# discretefpga.net
KiCad netlist of a schematic drawn in EAGLE
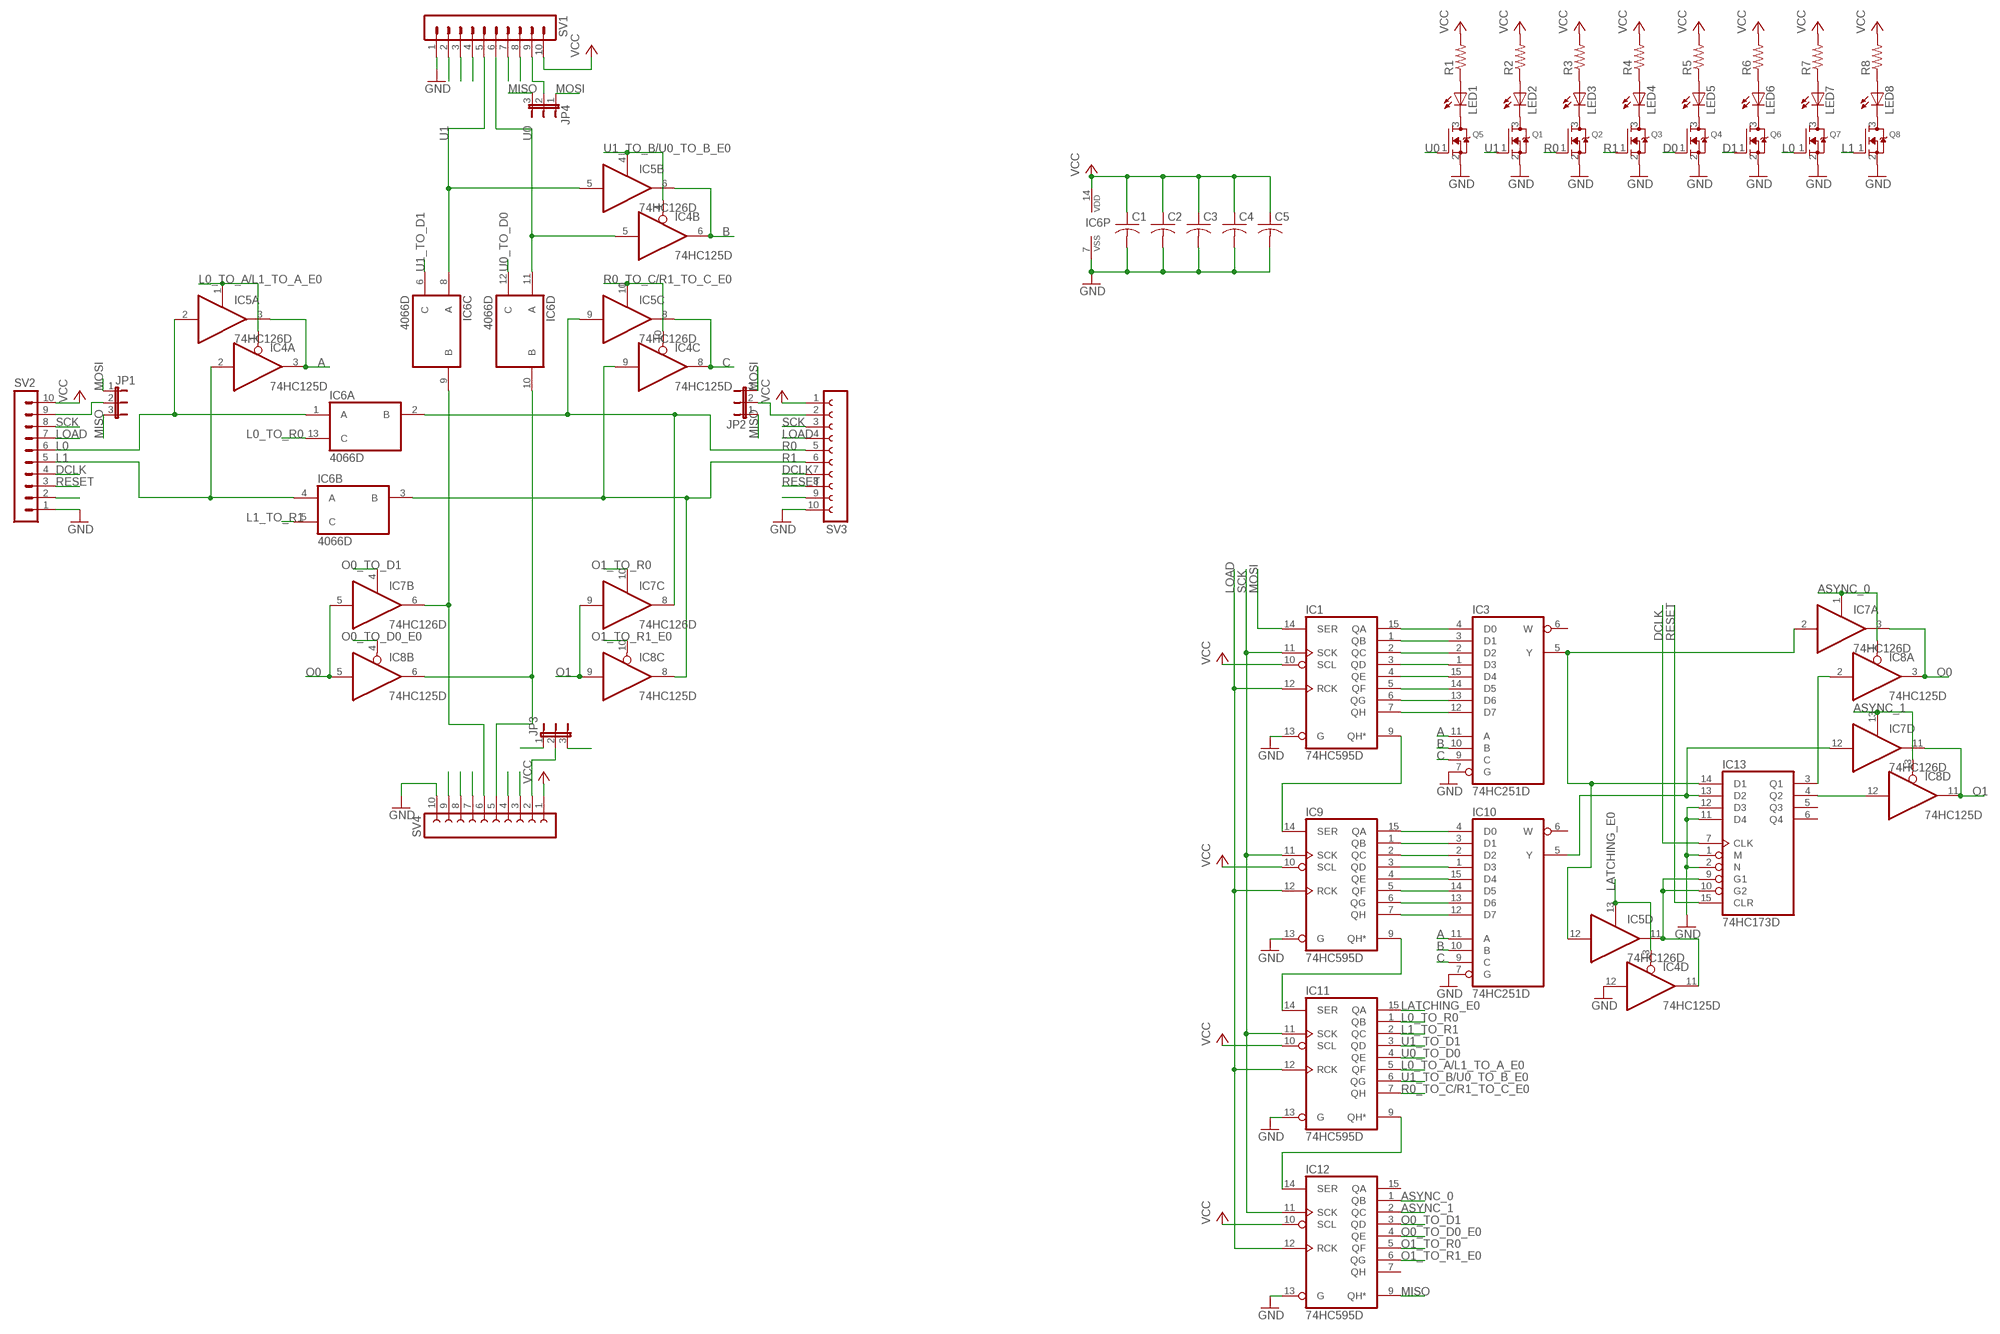
[diagram p0: schematic, sheet 1]

(export (version "E")
  (design (tool "Eeschema 10.0.6"))
  (components
    (comp (ref "C1")
      (value "C-USC0805")
      (footprint "eagle-import:C0805")
      (libsource (lib "eagle-import") (part "C-USC0805"))
    )
    (comp (ref "C2")
      (value "C-USC0805")
      (footprint "eagle-import:C0805")
      (libsource (lib "eagle-import") (part "C-USC0805"))
    )
    (comp (ref "C3")
      (value "C-USC0805")
      (footprint "eagle-import:C0805")
      (libsource (lib "eagle-import") (part "C-USC0805"))
    )
    (comp (ref "C4")
      (value "C-USC0805")
      (footprint "eagle-import:C0805")
      (libsource (lib "eagle-import") (part "C-USC0805"))
    )
    (comp (ref "C5")
      (value "C-USC0805")
      (footprint "eagle-import:C0805")
      (libsource (lib "eagle-import") (part "C-USC0805"))
    )
    (comp (ref "IC1")
      (value "74HC595D")
      (footprint "eagle-import:SO16")
      (libsource (lib "eagle-import") (part "74595DHC"))
    )
    (comp (ref "IC3")
      (value "74HC251D")
      (footprint "eagle-import:SO16")
      (libsource (lib "eagle-import") (part "74251DHC"))
    )
    (comp (ref "IC4")
      (value "74HC125D")
      (footprint "eagle-import:SO14")
      (libsource (lib "eagle-import") (part "74125DHC"))
    )
    (comp (ref "IC5")
      (value "74HC126D")
      (footprint "eagle-import:SO14")
      (libsource (lib "eagle-import") (part "74126DHC"))
    )
    (comp (ref "IC6")
      (value "4066D")
      (footprint "eagle-import:SO14")
      (libsource (lib "eagle-import") (part "4066D"))
    )
    (comp (ref "IC7")
      (value "74HC126D")
      (footprint "eagle-import:SO14")
      (libsource (lib "eagle-import") (part "74126DHC"))
    )
    (comp (ref "IC8")
      (value "74HC125D")
      (footprint "eagle-import:SO14")
      (libsource (lib "eagle-import") (part "74125DHC"))
    )
    (comp (ref "IC9")
      (value "74HC595D")
      (footprint "eagle-import:SO16")
      (libsource (lib "eagle-import") (part "74595DHC"))
    )
    (comp (ref "IC10")
      (value "74HC251D")
      (footprint "eagle-import:SO16")
      (libsource (lib "eagle-import") (part "74251DHC"))
    )
    (comp (ref "IC11")
      (value "74HC595D")
      (footprint "eagle-import:SO16")
      (libsource (lib "eagle-import") (part "74595DHC"))
    )
    (comp (ref "IC12")
      (value "74HC595D")
      (footprint "eagle-import:SO16")
      (libsource (lib "eagle-import") (part "74595DHC"))
    )
    (comp (ref "IC13")
      (value "74HC173D")
      (footprint "eagle-import:SO16")
      (libsource (lib "eagle-import") (part "74173DHC"))
    )
    (comp (ref "JP1")
      (value "JP2E")
      (footprint "eagle-import:JP2")
      (libsource (lib "eagle-import") (part "JP2E"))
    )
    (comp (ref "JP2")
      (value "JP2E")
      (footprint "eagle-import:JP2")
      (libsource (lib "eagle-import") (part "JP2E"))
    )
    (comp (ref "JP3")
      (value "JP2E")
      (footprint "eagle-import:JP2")
      (libsource (lib "eagle-import") (part "JP2E"))
    )
    (comp (ref "JP4")
      (value "JP2E")
      (footprint "eagle-import:JP2")
      (libsource (lib "eagle-import") (part "JP2E"))
    )
    (comp (ref "LED1")
      (value "LEDCHIP-LED0805")
      (footprint "eagle-import:CHIP-LED0805")
      (libsource (lib "eagle-import") (part "LEDCHIP-LED0805"))
    )
    (comp (ref "LED2")
      (value "LEDCHIP-LED0805")
      (footprint "eagle-import:CHIP-LED0805")
      (libsource (lib "eagle-import") (part "LEDCHIP-LED0805"))
    )
    (comp (ref "LED3")
      (value "LEDCHIP-LED0805")
      (footprint "eagle-import:CHIP-LED0805")
      (libsource (lib "eagle-import") (part "LEDCHIP-LED0805"))
    )
    (comp (ref "LED4")
      (value "LEDCHIP-LED0805")
      (footprint "eagle-import:CHIP-LED0805")
      (libsource (lib "eagle-import") (part "LEDCHIP-LED0805"))
    )
    (comp (ref "LED5")
      (value "LEDCHIP-LED0805")
      (footprint "eagle-import:CHIP-LED0805")
      (libsource (lib "eagle-import") (part "LEDCHIP-LED0805"))
    )
    (comp (ref "LED6")
      (value "LEDCHIP-LED0805")
      (footprint "eagle-import:CHIP-LED0805")
      (libsource (lib "eagle-import") (part "LEDCHIP-LED0805"))
    )
    (comp (ref "LED7")
      (value "LEDCHIP-LED0805")
      (footprint "eagle-import:CHIP-LED0805")
      (libsource (lib "eagle-import") (part "LEDCHIP-LED0805"))
    )
    (comp (ref "LED8")
      (value "LEDCHIP-LED0805")
      (footprint "eagle-import:CHIP-LED0805")
      (libsource (lib "eagle-import") (part "LEDCHIP-LED0805"))
    )
    (comp (ref "Q1")
      (value "MOSFET-NREFLOW")
      (footprint "eagle-import:SOT23")
      (libsource (lib "eagle-import") (part "MOSFET-NREFLOW"))
    )
    (comp (ref "Q2")
      (value "MOSFET-NREFLOW")
      (footprint "eagle-import:SOT23")
      (libsource (lib "eagle-import") (part "MOSFET-NREFLOW"))
    )
    (comp (ref "Q3")
      (value "MOSFET-NREFLOW")
      (footprint "eagle-import:SOT23")
      (libsource (lib "eagle-import") (part "MOSFET-NREFLOW"))
    )
    (comp (ref "Q4")
      (value "MOSFET-NREFLOW")
      (footprint "eagle-import:SOT23")
      (libsource (lib "eagle-import") (part "MOSFET-NREFLOW"))
    )
    (comp (ref "Q5")
      (value "MOSFET-NREFLOW")
      (footprint "eagle-import:SOT23")
      (libsource (lib "eagle-import") (part "MOSFET-NREFLOW"))
    )
    (comp (ref "Q6")
      (value "MOSFET-NREFLOW")
      (footprint "eagle-import:SOT23")
      (libsource (lib "eagle-import") (part "MOSFET-NREFLOW"))
    )
    (comp (ref "Q7")
      (value "MOSFET-NREFLOW")
      (footprint "eagle-import:SOT23")
      (libsource (lib "eagle-import") (part "MOSFET-NREFLOW"))
    )
    (comp (ref "Q8")
      (value "MOSFET-NREFLOW")
      (footprint "eagle-import:SOT23")
      (libsource (lib "eagle-import") (part "MOSFET-NREFLOW"))
    )
    (comp (ref "R1")
      (value "R-US_R0805")
      (footprint "eagle-import:R0805")
      (libsource (lib "eagle-import") (part "R-US_R0805"))
    )
    (comp (ref "R2")
      (value "R-US_R0805")
      (footprint "eagle-import:R0805")
      (libsource (lib "eagle-import") (part "R-US_R0805"))
    )
    (comp (ref "R3")
      (value "R-US_R0805")
      (footprint "eagle-import:R0805")
      (libsource (lib "eagle-import") (part "R-US_R0805"))
    )
    (comp (ref "R4")
      (value "R-US_R0805")
      (footprint "eagle-import:R0805")
      (libsource (lib "eagle-import") (part "R-US_R0805"))
    )
    (comp (ref "R5")
      (value "R-US_R0805")
      (footprint "eagle-import:R0805")
      (libsource (lib "eagle-import") (part "R-US_R0805"))
    )
    (comp (ref "R6")
      (value "R-US_R0805")
      (footprint "eagle-import:R0805")
      (libsource (lib "eagle-import") (part "R-US_R0805"))
    )
    (comp (ref "R7")
      (value "R-US_R0805")
      (footprint "eagle-import:R0805")
      (libsource (lib "eagle-import") (part "R-US_R0805"))
    )
    (comp (ref "R8")
      (value "R-US_R0805")
      (footprint "eagle-import:R0805")
      (libsource (lib "eagle-import") (part "R-US_R0805"))
    )
    (comp (ref "SV1")
      (value "MA10-1W")
      (footprint "eagle-import:MA10-1W")
      (libsource (lib "eagle-import") (part "MA10-1W"))
    )
    (comp (ref "SV2")
      (value "MA10-1W")
      (footprint "eagle-import:MA10-1W")
      (libsource (lib "eagle-import") (part "MA10-1W"))
    )
    (comp (ref "SV3")
      (value "FE10W")
      (footprint "eagle-import:FE10W")
      (libsource (lib "eagle-import") (part "FE10W"))
    )
    (comp (ref "SV4")
      (value "FE10W")
      (footprint "eagle-import:FE10W")
      (libsource (lib "eagle-import") (part "FE10W"))
    )
  )
  (nets
    (net (code "1") (name "/A") (class "Default")
      (node (ref "IC10") (pin "11") (pinfunction "A_11") (pintype "input"))
      (node (ref "IC3") (pin "11") (pinfunction "A_11") (pintype "input"))
      (node (ref "IC4") (pin "3") (pinfunction "O_3") (pintype "tri_state"))
      (node (ref "IC5") (pin "3") (pinfunction "O_3") (pintype "output"))
    )
    (net (code "2") (name "/ASYNC_0") (class "Default")
      (node (ref "IC12") (pin "1") (pinfunction "QB_1") (pintype "tri_state"))
      (node (ref "IC7") (pin "1") (pinfunction "OE_1") (pintype "input"))
      (node (ref "IC8") (pin "1") (pinfunction "OE_1") (pintype "input"))
    )
    (net (code "3") (name "/ASYNC_1") (class "Default")
      (node (ref "IC12") (pin "2") (pinfunction "QC_2") (pintype "tri_state"))
      (node (ref "IC7") (pin "13") (pinfunction "OE_13") (pintype "input"))
      (node (ref "IC8") (pin "13") (pinfunction "OE_13") (pintype "input"))
    )
    (net (code "4") (name "/B") (class "Default")
      (node (ref "IC10") (pin "10") (pinfunction "B_10") (pintype "input"))
      (node (ref "IC3") (pin "10") (pinfunction "B_10") (pintype "input"))
      (node (ref "IC4") (pin "6") (pinfunction "O_6") (pintype "tri_state"))
      (node (ref "IC5") (pin "6") (pinfunction "O_6") (pintype "output"))
    )
    (net (code "5") (name "/C") (class "Default")
      (node (ref "IC10") (pin "9") (pinfunction "C_9") (pintype "input"))
      (node (ref "IC3") (pin "9") (pinfunction "C_9") (pintype "input"))
      (node (ref "IC4") (pin "8") (pinfunction "O_8") (pintype "tri_state"))
      (node (ref "IC5") (pin "8") (pinfunction "O_8") (pintype "output"))
    )
    (net (code "6") (name "/D0") (class "Default")
      (node (ref "IC6") (pin "10") (pinfunction "B_10") (pintype "tri_state"))
      (node (ref "IC8") (pin "6") (pinfunction "O_6") (pintype "tri_state"))
      (node (ref "Q4") (pin "1") (pinfunction "G_1") (pintype "bidirectional"))
      (node (ref "SV4") (pin "5") (pinfunction "5_5") (pintype "passive"))
    )
    (net (code "7") (name "/D1") (class "Default")
      (node (ref "IC6") (pin "9") (pinfunction "B_9") (pintype "tri_state"))
      (node (ref "IC7") (pin "6") (pinfunction "O_6") (pintype "output"))
      (node (ref "Q6") (pin "1") (pinfunction "G_1") (pintype "bidirectional"))
      (node (ref "SV4") (pin "6") (pinfunction "6_6") (pintype "passive"))
    )
    (net (code "8") (name "/DCLK") (class "Default")
      (node (ref "IC13") (pin "7") (pinfunction "CLK_7") (pintype "input"))
      (node (ref "SV1") (pin "4") (pinfunction "4_4") (pintype "passive"))
      (node (ref "SV2") (pin "4") (pinfunction "4_4") (pintype "passive"))
      (node (ref "SV3") (pin "7") (pinfunction "7_7") (pintype "passive"))
      (node (ref "SV4") (pin "7") (pinfunction "7_7") (pintype "passive"))
    )
    (net (code "9") (name "/L0") (class "Default")
      (node (ref "IC5") (pin "2") (pinfunction "I_2") (pintype "input"))
      (node (ref "IC6") (pin "1") (pinfunction "A_1") (pintype "tri_state"))
      (node (ref "Q7") (pin "1") (pinfunction "G_1") (pintype "bidirectional"))
      (node (ref "SV2") (pin "6") (pinfunction "6_6") (pintype "passive"))
    )
    (net (code "10") (name "/L0_TO_A{slash}L1_TO_A_E0") (class "Default")
      (node (ref "IC11") (pin "5") (pinfunction "QF_5") (pintype "tri_state"))
      (node (ref "IC4") (pin "1") (pinfunction "OE_1") (pintype "input"))
      (node (ref "IC5") (pin "1") (pinfunction "OE_1") (pintype "input"))
    )
    (net (code "11") (name "/L0_TO_R0") (class "Default")
      (node (ref "IC11") (pin "1") (pinfunction "QB_1") (pintype "tri_state"))
      (node (ref "IC6") (pin "13") (pinfunction "C_13") (pintype "input"))
    )
    (net (code "12") (name "/L1") (class "Default")
      (node (ref "IC4") (pin "2") (pinfunction "I_2") (pintype "input"))
      (node (ref "IC6") (pin "4") (pinfunction "A_4") (pintype "tri_state"))
      (node (ref "Q8") (pin "1") (pinfunction "G_1") (pintype "bidirectional"))
      (node (ref "SV2") (pin "5") (pinfunction "5_5") (pintype "passive"))
    )
    (net (code "13") (name "/L1_TO_R1") (class "Default")
      (node (ref "IC11") (pin "2") (pinfunction "QC_2") (pintype "tri_state"))
      (node (ref "IC6") (pin "5") (pinfunction "C_5") (pintype "input"))
    )
    (net (code "14") (name "/LATCHING_E0") (class "Default")
      (node (ref "IC11") (pin "15") (pinfunction "QA_15") (pintype "tri_state"))
      (node (ref "IC4") (pin "13") (pinfunction "OE_13") (pintype "input"))
      (node (ref "IC5") (pin "13") (pinfunction "OE_13") (pintype "input"))
    )
    (net (code "15") (name "/LOAD") (class "Default")
      (node (ref "IC1") (pin "12") (pinfunction "RCK_12") (pintype "input"))
      (node (ref "IC11") (pin "12") (pinfunction "RCK_12") (pintype "input"))
      (node (ref "IC12") (pin "12") (pinfunction "RCK_12") (pintype "input"))
      (node (ref "IC9") (pin "12") (pinfunction "RCK_12") (pintype "input"))
      (node (ref "SV1") (pin "7") (pinfunction "7_7") (pintype "passive"))
      (node (ref "SV2") (pin "7") (pinfunction "7_7") (pintype "passive"))
      (node (ref "SV3") (pin "4") (pinfunction "4_4") (pintype "passive"))
      (node (ref "SV4") (pin "4") (pinfunction "4_4") (pintype "passive"))
    )
    (net (code "16") (name "/MISO") (class "Default")
      (node (ref "IC12") (pin "9") (pinfunction "QH*_9") (pintype "tri_state"))
      (node (ref "JP1") (pin "3") (pinfunction "3_3") (pintype "passive"))
      (node (ref "JP2") (pin "1") (pinfunction "1_1") (pintype "passive"))
      (node (ref "JP3") (pin "1") (pinfunction "1_1") (pintype "passive"))
      (node (ref "JP4") (pin "3") (pinfunction "3_3") (pintype "passive"))
    )
    (net (code "17") (name "/MOSI") (class "Default")
      (node (ref "IC1") (pin "14") (pinfunction "SER_14") (pintype "input"))
      (node (ref "JP1") (pin "1") (pinfunction "1_1") (pintype "passive"))
      (node (ref "JP2") (pin "3") (pinfunction "3_3") (pintype "passive"))
      (node (ref "JP3") (pin "3") (pinfunction "3_3") (pintype "passive"))
      (node (ref "JP4") (pin "1") (pinfunction "1_1") (pintype "passive"))
    )
    (net (code "18") (name "/O0") (class "Default")
      (node (ref "IC7") (pin "3") (pinfunction "O_3") (pintype "output"))
      (node (ref "IC7") (pin "5") (pinfunction "I_5") (pintype "input"))
      (node (ref "IC8") (pin "3") (pinfunction "O_3") (pintype "tri_state"))
      (node (ref "IC8") (pin "5") (pinfunction "I_5") (pintype "input"))
    )
    (net (code "19") (name "/O0_TO_D0_E0") (class "Default")
      (node (ref "IC12") (pin "4") (pinfunction "QE_4") (pintype "tri_state"))
      (node (ref "IC8") (pin "4") (pinfunction "OE_4") (pintype "input"))
    )
    (net (code "20") (name "/O0_TO_D1") (class "Default")
      (node (ref "IC12") (pin "3") (pinfunction "QD_3") (pintype "tri_state"))
      (node (ref "IC7") (pin "4") (pinfunction "OE_4") (pintype "input"))
    )
    (net (code "21") (name "/O1") (class "Default")
      (node (ref "IC7") (pin "11") (pinfunction "O_11") (pintype "output"))
      (node (ref "IC7") (pin "9") (pinfunction "I_9") (pintype "input"))
      (node (ref "IC8") (pin "11") (pinfunction "O_11") (pintype "tri_state"))
      (node (ref "IC8") (pin "9") (pinfunction "I_9") (pintype "input"))
    )
    (net (code "22") (name "/O1_TO_R0") (class "Default")
      (node (ref "IC12") (pin "5") (pinfunction "QF_5") (pintype "tri_state"))
      (node (ref "IC7") (pin "10") (pinfunction "OE_10") (pintype "input"))
    )
    (net (code "23") (name "/O1_TO_R1_E0") (class "Default")
      (node (ref "IC12") (pin "6") (pinfunction "QG_6") (pintype "tri_state"))
      (node (ref "IC8") (pin "10") (pinfunction "OE_10") (pintype "input"))
    )
    (net (code "24") (name "/R0") (class "Default")
      (node (ref "IC5") (pin "9") (pinfunction "I_9") (pintype "input"))
      (node (ref "IC6") (pin "2") (pinfunction "B_2") (pintype "tri_state"))
      (node (ref "IC7") (pin "8") (pinfunction "O_8") (pintype "output"))
      (node (ref "Q2") (pin "1") (pinfunction "G_1") (pintype "bidirectional"))
      (node (ref "SV3") (pin "5") (pinfunction "5_5") (pintype "passive"))
    )
    (net (code "25") (name "/R0_TO_C{slash}R1_TO_C_E0") (class "Default")
      (node (ref "IC11") (pin "7") (pinfunction "QH_7") (pintype "tri_state"))
      (node (ref "IC4") (pin "10") (pinfunction "OE_10") (pintype "input"))
      (node (ref "IC5") (pin "10") (pinfunction "OE_10") (pintype "input"))
    )
    (net (code "26") (name "/R1") (class "Default")
      (node (ref "IC4") (pin "9") (pinfunction "I_9") (pintype "input"))
      (node (ref "IC6") (pin "3") (pinfunction "B_3") (pintype "tri_state"))
      (node (ref "IC8") (pin "8") (pinfunction "O_8") (pintype "tri_state"))
      (node (ref "Q3") (pin "1") (pinfunction "G_1") (pintype "bidirectional"))
      (node (ref "SV3") (pin "6") (pinfunction "6_6") (pintype "passive"))
    )
    (net (code "27") (name "/RESET") (class "Default")
      (node (ref "IC13") (pin "15") (pinfunction "CLR_15") (pintype "input"))
      (node (ref "SV1") (pin "3") (pinfunction "3_3") (pintype "passive"))
      (node (ref "SV2") (pin "3") (pinfunction "3_3") (pintype "passive"))
      (node (ref "SV3") (pin "8") (pinfunction "8_8") (pintype "passive"))
      (node (ref "SV4") (pin "8") (pinfunction "8_8") (pintype "passive"))
    )
    (net (code "28") (name "/SCK") (class "Default")
      (node (ref "IC1") (pin "11") (pinfunction "SCK_11") (pintype "input"))
      (node (ref "IC11") (pin "11") (pinfunction "SCK_11") (pintype "input"))
      (node (ref "IC12") (pin "11") (pinfunction "SCK_11") (pintype "input"))
      (node (ref "IC9") (pin "11") (pinfunction "SCK_11") (pintype "input"))
      (node (ref "SV1") (pin "8") (pinfunction "8_8") (pintype "passive"))
      (node (ref "SV2") (pin "8") (pinfunction "8_8") (pintype "passive"))
      (node (ref "SV3") (pin "3") (pinfunction "3_3") (pintype "passive"))
      (node (ref "SV4") (pin "3") (pinfunction "3_3") (pintype "passive"))
    )
    (net (code "29") (name "/U0") (class "Default")
      (node (ref "IC4") (pin "5") (pinfunction "I_5") (pintype "input"))
      (node (ref "IC6") (pin "11") (pinfunction "A_11") (pintype "tri_state"))
      (node (ref "Q5") (pin "1") (pinfunction "G_1") (pintype "bidirectional"))
      (node (ref "SV1") (pin "6") (pinfunction "6_6") (pintype "passive"))
    )
    (net (code "30") (name "/U0_TO_D0") (class "Default")
      (node (ref "IC11") (pin "4") (pinfunction "QE_4") (pintype "tri_state"))
      (node (ref "IC6") (pin "12") (pinfunction "C_12") (pintype "input"))
    )
    (net (code "31") (name "/U1") (class "Default")
      (node (ref "IC5") (pin "5") (pinfunction "I_5") (pintype "input"))
      (node (ref "IC6") (pin "8") (pinfunction "A_8") (pintype "tri_state"))
      (node (ref "Q1") (pin "1") (pinfunction "G_1") (pintype "bidirectional"))
      (node (ref "SV1") (pin "5") (pinfunction "5_5") (pintype "passive"))
    )
    (net (code "32") (name "/U1_TO_B{slash}U0_TO_B_E0") (class "Default")
      (node (ref "IC11") (pin "6") (pinfunction "QG_6") (pintype "tri_state"))
      (node (ref "IC4") (pin "4") (pinfunction "OE_4") (pintype "input"))
      (node (ref "IC5") (pin "4") (pinfunction "OE_4") (pintype "input"))
    )
    (net (code "33") (name "/U1_TO_D1") (class "Default")
      (node (ref "IC11") (pin "3") (pinfunction "QD_3") (pintype "tri_state"))
      (node (ref "IC6") (pin "6") (pinfunction "C_6") (pintype "input"))
    )
    (net (code "34") (name "GND") (class "Default")
      (node (ref "C1") (pin "2") (pinfunction "2_2") (pintype "passive"))
      (node (ref "C2") (pin "2") (pinfunction "2_2") (pintype "passive"))
      (node (ref "C3") (pin "2") (pinfunction "2_2") (pintype "passive"))
      (node (ref "C4") (pin "2") (pinfunction "2_2") (pintype "passive"))
      (node (ref "C5") (pin "2") (pinfunction "2_2") (pintype "passive"))
      (node (ref "IC1") (pin "13") (pinfunction "G_13") (pintype "input"))
      (node (ref "IC10") (pin "7") (pinfunction "G_7") (pintype "input"))
      (node (ref "IC11") (pin "13") (pinfunction "G_13") (pintype "input"))
      (node (ref "IC12") (pin "13") (pinfunction "G_13") (pintype "input"))
      (node (ref "IC13") (pin "1") (pinfunction "M_1") (pintype "input"))
      (node (ref "IC13") (pin "11") (pinfunction "D4_11") (pintype "input"))
      (node (ref "IC13") (pin "12") (pinfunction "D3_12") (pintype "input"))
      (node (ref "IC13") (pin "2") (pinfunction "N_2") (pintype "input"))
      (node (ref "IC3") (pin "7") (pinfunction "G_7") (pintype "input"))
      (node (ref "IC4") (pin "12") (pinfunction "I_12") (pintype "input"))
      (node (ref "IC6") (pin "7") (pinfunction "VSS_7") (pintype "power_in"))
      (node (ref "IC9") (pin "13") (pinfunction "G_13") (pintype "input"))
      (node (ref "Q1") (pin "2") (pinfunction "S_2") (pintype "bidirectional"))
      (node (ref "Q2") (pin "2") (pinfunction "S_2") (pintype "bidirectional"))
      (node (ref "Q3") (pin "2") (pinfunction "S_2") (pintype "bidirectional"))
      (node (ref "Q4") (pin "2") (pinfunction "S_2") (pintype "bidirectional"))
      (node (ref "Q5") (pin "2") (pinfunction "S_2") (pintype "bidirectional"))
      (node (ref "Q6") (pin "2") (pinfunction "S_2") (pintype "bidirectional"))
      (node (ref "Q7") (pin "2") (pinfunction "S_2") (pintype "bidirectional"))
      (node (ref "Q8") (pin "2") (pinfunction "S_2") (pintype "bidirectional"))
      (node (ref "SV1") (pin "1") (pinfunction "1_1") (pintype "passive"))
      (node (ref "SV2") (pin "1") (pinfunction "1_1") (pintype "passive"))
      (node (ref "SV3") (pin "10") (pinfunction "10_10") (pintype "passive"))
      (node (ref "SV4") (pin "10") (pinfunction "10_10") (pintype "passive"))
    )
    (net (code "35") (name "Net-(IC1A-QA)") (class "Default")
      (node (ref "IC1") (pin "15") (pinfunction "QA_15") (pintype "tri_state"))
      (node (ref "IC3") (pin "4") (pinfunction "D0_4") (pintype "input"))
    )
    (net (code "36") (name "Net-(IC1A-QB)") (class "Default")
      (node (ref "IC1") (pin "1") (pinfunction "QB_1") (pintype "tri_state"))
      (node (ref "IC3") (pin "3") (pinfunction "D1_3") (pintype "input"))
    )
    (net (code "37") (name "Net-(IC1A-QC)") (class "Default")
      (node (ref "IC1") (pin "2") (pinfunction "QC_2") (pintype "tri_state"))
      (node (ref "IC3") (pin "2") (pinfunction "D2_2") (pintype "input"))
    )
    (net (code "38") (name "Net-(IC1A-QD)") (class "Default")
      (node (ref "IC1") (pin "3") (pinfunction "QD_3") (pintype "tri_state"))
      (node (ref "IC3") (pin "1") (pinfunction "D3_1") (pintype "input"))
    )
    (net (code "39") (name "Net-(IC1A-QE)") (class "Default")
      (node (ref "IC1") (pin "4") (pinfunction "QE_4") (pintype "tri_state"))
      (node (ref "IC3") (pin "15") (pinfunction "D4_15") (pintype "input"))
    )
    (net (code "40") (name "Net-(IC1A-QF)") (class "Default")
      (node (ref "IC1") (pin "5") (pinfunction "QF_5") (pintype "tri_state"))
      (node (ref "IC3") (pin "14") (pinfunction "D5_14") (pintype "input"))
    )
    (net (code "41") (name "Net-(IC1A-QG)") (class "Default")
      (node (ref "IC1") (pin "6") (pinfunction "QG_6") (pintype "tri_state"))
      (node (ref "IC3") (pin "13") (pinfunction "D6_13") (pintype "input"))
    )
    (net (code "42") (name "Net-(IC1A-QH)") (class "Default")
      (node (ref "IC1") (pin "7") (pinfunction "QH_7") (pintype "tri_state"))
      (node (ref "IC3") (pin "12") (pinfunction "D7_12") (pintype "input"))
    )
    (net (code "43") (name "Net-(IC1A-QH*)") (class "Default")
      (node (ref "IC1") (pin "9") (pinfunction "QH*_9") (pintype "tri_state"))
      (node (ref "IC9") (pin "14") (pinfunction "SER_14") (pintype "input"))
    )
    (net (code "44") (name "Net-(IC10A-D0)") (class "Default")
      (node (ref "IC10") (pin "4") (pinfunction "D0_4") (pintype "input"))
      (node (ref "IC9") (pin "15") (pinfunction "QA_15") (pintype "tri_state"))
    )
    (net (code "45") (name "Net-(IC10A-D1)") (class "Default")
      (node (ref "IC10") (pin "3") (pinfunction "D1_3") (pintype "input"))
      (node (ref "IC9") (pin "1") (pinfunction "QB_1") (pintype "tri_state"))
    )
    (net (code "46") (name "Net-(IC10A-D2)") (class "Default")
      (node (ref "IC10") (pin "2") (pinfunction "D2_2") (pintype "input"))
      (node (ref "IC9") (pin "2") (pinfunction "QC_2") (pintype "tri_state"))
    )
    (net (code "47") (name "Net-(IC10A-D3)") (class "Default")
      (node (ref "IC10") (pin "1") (pinfunction "D3_1") (pintype "input"))
      (node (ref "IC9") (pin "3") (pinfunction "QD_3") (pintype "tri_state"))
    )
    (net (code "48") (name "Net-(IC10A-D4)") (class "Default")
      (node (ref "IC10") (pin "15") (pinfunction "D4_15") (pintype "input"))
      (node (ref "IC9") (pin "4") (pinfunction "QE_4") (pintype "tri_state"))
    )
    (net (code "49") (name "Net-(IC10A-D5)") (class "Default")
      (node (ref "IC10") (pin "14") (pinfunction "D5_14") (pintype "input"))
      (node (ref "IC9") (pin "5") (pinfunction "QF_5") (pintype "tri_state"))
    )
    (net (code "50") (name "Net-(IC10A-D6)") (class "Default")
      (node (ref "IC10") (pin "13") (pinfunction "D6_13") (pintype "input"))
      (node (ref "IC9") (pin "6") (pinfunction "QG_6") (pintype "tri_state"))
    )
    (net (code "51") (name "Net-(IC10A-D7)") (class "Default")
      (node (ref "IC10") (pin "12") (pinfunction "D7_12") (pintype "input"))
      (node (ref "IC9") (pin "7") (pinfunction "QH_7") (pintype "tri_state"))
    )
    (net (code "52") (name "Net-(IC10A-Y)") (class "Default")
      (node (ref "IC10") (pin "5") (pinfunction "Y_5") (pintype "tri_state"))
      (node (ref "IC13") (pin "13") (pinfunction "D2_13") (pintype "input"))
      (node (ref "IC7") (pin "12") (pinfunction "I_12") (pintype "input"))
    )
    (net (code "53") (name "Net-(IC11A-QH*)") (class "Default")
      (node (ref "IC11") (pin "9") (pinfunction "QH*_9") (pintype "tri_state"))
      (node (ref "IC12") (pin "14") (pinfunction "SER_14") (pintype "input"))
    )
    (net (code "54") (name "Net-(IC11A-SER)") (class "Default")
      (node (ref "IC11") (pin "14") (pinfunction "SER_14") (pintype "input"))
      (node (ref "IC9") (pin "9") (pinfunction "QH*_9") (pintype "tri_state"))
    )
    (net (code "55") (name "Net-(IC13A-D1)") (class "Default")
      (node (ref "IC13") (pin "14") (pinfunction "D1_14") (pintype "input"))
      (node (ref "IC3") (pin "5") (pinfunction "Y_5") (pintype "tri_state"))
      (node (ref "IC5") (pin "12") (pinfunction "I_12") (pintype "input"))
      (node (ref "IC7") (pin "2") (pinfunction "I_2") (pintype "input"))
    )
    (net (code "56") (name "Net-(IC13A-G1)") (class "Default")
      (node (ref "IC13") (pin "10") (pinfunction "G2_10") (pintype "input"))
      (node (ref "IC13") (pin "9") (pinfunction "G1_9") (pintype "input"))
      (node (ref "IC4") (pin "11") (pinfunction "O_11") (pintype "tri_state"))
      (node (ref "IC5") (pin "11") (pinfunction "O_11") (pintype "output"))
    )
    (net (code "57") (name "Net-(IC13A-Q1)") (class "Default")
      (node (ref "IC13") (pin "3") (pinfunction "Q1_3") (pintype "tri_state"))
      (node (ref "IC8") (pin "2") (pinfunction "I_2") (pintype "input"))
    )
    (net (code "58") (name "Net-(IC13A-Q2)") (class "Default")
      (node (ref "IC13") (pin "4") (pinfunction "Q2_4") (pintype "tri_state"))
      (node (ref "IC8") (pin "12") (pinfunction "I_12") (pintype "input"))
    )
    (net (code "59") (name "Net-(JP1-Pad2)") (class "Default")
      (node (ref "JP1") (pin "2") (pinfunction "2_2") (pintype "passive"))
      (node (ref "SV2") (pin "9") (pinfunction "9_9") (pintype "passive"))
    )
    (net (code "60") (name "Net-(JP2-Pad2)") (class "Default")
      (node (ref "JP2") (pin "2") (pinfunction "2_2") (pintype "passive"))
      (node (ref "SV3") (pin "2") (pinfunction "2_2") (pintype "passive"))
    )
    (net (code "61") (name "Net-(JP3-Pad2)") (class "Default")
      (node (ref "JP3") (pin "2") (pinfunction "2_2") (pintype "passive"))
      (node (ref "SV4") (pin "2") (pinfunction "2_2") (pintype "passive"))
    )
    (net (code "62") (name "Net-(JP4-Pad2)") (class "Default")
      (node (ref "JP4") (pin "2") (pinfunction "2_2") (pintype "passive"))
      (node (ref "SV1") (pin "9") (pinfunction "9_9") (pintype "passive"))
    )
    (net (code "63") (name "Net-(LED1-PadA)") (class "Default")
      (node (ref "LED1") (pin "A") (pinfunction "A_A") (pintype "passive"))
      (node (ref "R1") (pin "1") (pinfunction "1_1") (pintype "passive"))
    )
    (net (code "64") (name "Net-(LED2-PadA)") (class "Default")
      (node (ref "LED2") (pin "A") (pinfunction "A_A") (pintype "passive"))
      (node (ref "R2") (pin "1") (pinfunction "1_1") (pintype "passive"))
    )
    (net (code "65") (name "Net-(LED3-PadA)") (class "Default")
      (node (ref "LED3") (pin "A") (pinfunction "A_A") (pintype "passive"))
      (node (ref "R3") (pin "1") (pinfunction "1_1") (pintype "passive"))
    )
    (net (code "66") (name "Net-(LED4-PadA)") (class "Default")
      (node (ref "LED4") (pin "A") (pinfunction "A_A") (pintype "passive"))
      (node (ref "R4") (pin "1") (pinfunction "1_1") (pintype "passive"))
    )
    (net (code "67") (name "Net-(LED5-PadA)") (class "Default")
      (node (ref "LED5") (pin "A") (pinfunction "A_A") (pintype "passive"))
      (node (ref "R5") (pin "1") (pinfunction "1_1") (pintype "passive"))
    )
    (net (code "68") (name "Net-(LED6-PadA)") (class "Default")
      (node (ref "LED6") (pin "A") (pinfunction "A_A") (pintype "passive"))
      (node (ref "R6") (pin "1") (pinfunction "1_1") (pintype "passive"))
    )
    (net (code "69") (name "Net-(LED7-PadA)") (class "Default")
      (node (ref "LED7") (pin "A") (pinfunction "A_A") (pintype "passive"))
      (node (ref "R7") (pin "1") (pinfunction "1_1") (pintype "passive"))
    )
    (net (code "70") (name "Net-(LED8-PadA)") (class "Default")
      (node (ref "LED8") (pin "A") (pinfunction "A_A") (pintype "passive"))
      (node (ref "R8") (pin "1") (pinfunction "1_1") (pintype "passive"))
    )
    (net (code "71") (name "Net-(Q1-D)") (class "Default")
      (node (ref "LED2") (pin "C") (pinfunction "C_C") (pintype "passive"))
      (node (ref "Q1") (pin "3") (pinfunction "D_3") (pintype "bidirectional"))
    )
    (net (code "72") (name "Net-(Q2-D)") (class "Default")
      (node (ref "LED3") (pin "C") (pinfunction "C_C") (pintype "passive"))
      (node (ref "Q2") (pin "3") (pinfunction "D_3") (pintype "bidirectional"))
    )
    (net (code "73") (name "Net-(Q3-D)") (class "Default")
      (node (ref "LED4") (pin "C") (pinfunction "C_C") (pintype "passive"))
      (node (ref "Q3") (pin "3") (pinfunction "D_3") (pintype "bidirectional"))
    )
    (net (code "74") (name "Net-(Q4-D)") (class "Default")
      (node (ref "LED5") (pin "C") (pinfunction "C_C") (pintype "passive"))
      (node (ref "Q4") (pin "3") (pinfunction "D_3") (pintype "bidirectional"))
    )
    (net (code "75") (name "Net-(Q5-D)") (class "Default")
      (node (ref "LED1") (pin "C") (pinfunction "C_C") (pintype "passive"))
      (node (ref "Q5") (pin "3") (pinfunction "D_3") (pintype "bidirectional"))
    )
    (net (code "76") (name "Net-(Q6-D)") (class "Default")
      (node (ref "LED6") (pin "C") (pinfunction "C_C") (pintype "passive"))
      (node (ref "Q6") (pin "3") (pinfunction "D_3") (pintype "bidirectional"))
    )
    (net (code "77") (name "Net-(Q7-D)") (class "Default")
      (node (ref "LED7") (pin "C") (pinfunction "C_C") (pintype "passive"))
      (node (ref "Q7") (pin "3") (pinfunction "D_3") (pintype "bidirectional"))
    )
    (net (code "78") (name "Net-(Q8-D)") (class "Default")
      (node (ref "LED8") (pin "C") (pinfunction "C_C") (pintype "passive"))
      (node (ref "Q8") (pin "3") (pinfunction "D_3") (pintype "bidirectional"))
    )
    (net (code "79") (name "VCC") (class "Default")
      (node (ref "C1") (pin "1") (pinfunction "1_1") (pintype "passive"))
      (node (ref "C2") (pin "1") (pinfunction "1_1") (pintype "passive"))
      (node (ref "C3") (pin "1") (pinfunction "1_1") (pintype "passive"))
      (node (ref "C4") (pin "1") (pinfunction "1_1") (pintype "passive"))
      (node (ref "C5") (pin "1") (pinfunction "1_1") (pintype "passive"))
      (node (ref "IC1") (pin "10") (pinfunction "SCL_10") (pintype "input"))
      (node (ref "IC11") (pin "10") (pinfunction "SCL_10") (pintype "input"))
      (node (ref "IC12") (pin "10") (pinfunction "SCL_10") (pintype "input"))
      (node (ref "IC6") (pin "14") (pinfunction "VDD_14") (pintype "power_in"))
      (node (ref "IC9") (pin "10") (pinfunction "SCL_10") (pintype "input"))
      (node (ref "R1") (pin "2") (pinfunction "2_2") (pintype "passive"))
      (node (ref "R2") (pin "2") (pinfunction "2_2") (pintype "passive"))
      (node (ref "R3") (pin "2") (pinfunction "2_2") (pintype "passive"))
      (node (ref "R4") (pin "2") (pinfunction "2_2") (pintype "passive"))
      (node (ref "R5") (pin "2") (pinfunction "2_2") (pintype "passive"))
      (node (ref "R6") (pin "2") (pinfunction "2_2") (pintype "passive"))
      (node (ref "R7") (pin "2") (pinfunction "2_2") (pintype "passive"))
      (node (ref "R8") (pin "2") (pinfunction "2_2") (pintype "passive"))
      (node (ref "SV1") (pin "10") (pinfunction "10_10") (pintype "passive"))
      (node (ref "SV2") (pin "10") (pinfunction "10_10") (pintype "passive"))
      (node (ref "SV3") (pin "1") (pinfunction "1_1") (pintype "passive"))
      (node (ref "SV4") (pin "1") (pinfunction "1_1") (pintype "passive"))
    )
    (net (code "80") (name "unconnected-(IC3A-W-Pad6)") (class "Default")
      (node (ref "IC3") (pin "6") (pinfunction "W_6") (pintype "tri_state"))
    )
    (net (code "81") (name "unconnected-(IC10A-W-Pad6)") (class "Default")
      (node (ref "IC10") (pin "6") (pinfunction "W_6") (pintype "tri_state"))
    )
    (net (code "82") (name "unconnected-(IC12A-QA-Pad15)") (class "Default")
      (node (ref "IC12") (pin "15") (pinfunction "QA_15") (pintype "tri_state"))
    )
    (net (code "83") (name "unconnected-(IC12A-QH-Pad7)") (class "Default")
      (node (ref "IC12") (pin "7") (pinfunction "QH_7") (pintype "tri_state"))
    )
    (net (code "84") (name "unconnected-(IC13A-Q3-Pad5)") (class "Default")
      (node (ref "IC13") (pin "5") (pinfunction "Q3_5") (pintype "tri_state"))
    )
    (net (code "85") (name "unconnected-(IC13A-Q4-Pad6)") (class "Default")
      (node (ref "IC13") (pin "6") (pinfunction "Q4_6") (pintype "tri_state"))
    )
    (net (code "86") (name "unconnected-(SV1-Pad2)") (class "Default")
      (node (ref "SV1") (pin "2") (pinfunction "2_2") (pintype "passive"))
    )
    (net (code "87") (name "unconnected-(SV2-Pad2)") (class "Default")
      (node (ref "SV2") (pin "2") (pinfunction "2_2") (pintype "passive"))
    )
    (net (code "88") (name "unconnected-(SV3-Pad9)") (class "Default")
      (node (ref "SV3") (pin "9") (pinfunction "9_9") (pintype "passive"))
    )
    (net (code "89") (name "unconnected-(SV4-Pad9)") (class "Default")
      (node (ref "SV4") (pin "9") (pinfunction "9_9") (pintype "passive"))
    )
  )
)
